# Sheet3.net
KiCad netlist of a schematic drawn in Altium Designer
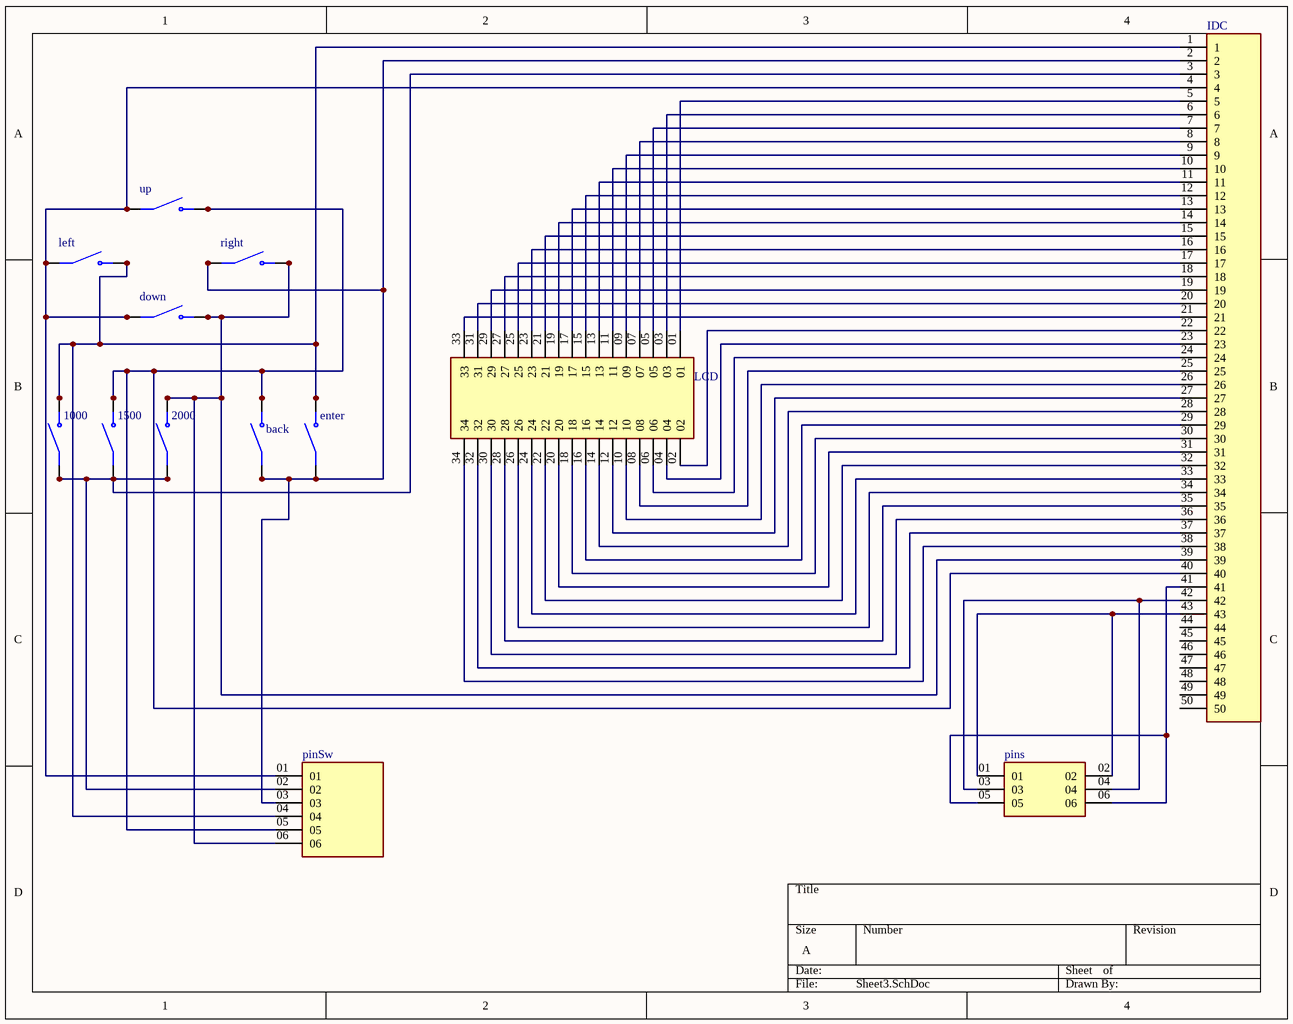
[diagram p0: Sheet3.SchDoc]

(export (version "E")
  (design (tool "Eeschema 10.0.6"))
  (components
    (comp (ref "1000")
      (value "4-1437565-9")
      (footprint "SW_4-1437565-9")
      (fields (field (name "MF") "TE Connectivity"))
      (libsource (lib "sw4") (part "4-1437565-9"))
    )
    (comp (ref "1500")
      (value "4-1437565-9")
      (footprint "SW_4-1437565-9")
      (fields (field (name "MF") "TE Connectivity"))
      (libsource (lib "sw4") (part "4-1437565-9"))
    )
    (comp (ref "2000")
      (value "4-1437565-9")
      (footprint "SW_4-1437565-9")
      (fields (field (name "MF") "TE Connectivity"))
      (libsource (lib "sw4") (part "4-1437565-9"))
    )
    (comp (ref "back")
      (value "4-1437565-9")
      (footprint "SW_4-1437565-9")
      (fields (field (name "MF") "TE Connectivity"))
      (libsource (lib "sw4") (part "4-1437565-9"))
    )
    (comp (ref "down")
      (value "4-1437565-9")
      (footprint "SW_4-1437565-9")
      (fields (field (name "MF") "TE Connectivity"))
      (libsource (lib "sw4") (part "4-1437565-9"))
    )
    (comp (ref "enter")
      (value "4-1437565-9")
      (footprint "SW_4-1437565-9")
      (fields (field (name "MF") "TE Connectivity"))
      (libsource (lib "sw4") (part "4-1437565-9"))
    )
    (comp (ref "IDC")
      (value "1-1761686-5")
      (footprint "TE_1-1761686-5")
      (libsource (lib "50pin") (part "1-1761686-5"))
    )
    (comp (ref "LCD")
      (value "TSW-117-23-G-D")
      (footprint "SAMTEC_TSW-117-23-G-D")
      (libsource (lib "pinhdr34") (part "TSW-117-23-G-D"))
    )
    (comp (ref "left")
      (value "4-1437565-9")
      (footprint "SW_4-1437565-9")
      (fields (field (name "MF") "TE Connectivity"))
      (libsource (lib "sw4") (part "4-1437565-9"))
    )
    (comp (ref "pins")
      (value "MTLW-103-07-L-D-320")
      (footprint "SAMTEC_MTLW-103-07-L-D-320")
      (libsource (lib "6pinhdr") (part "MTLW-103-07-L-D-320"))
    )
    (comp (ref "pinSw")
      (value "MTLW-106-05-T-S-137")
      (footprint "SAMTEC_MTLW-106-05-T-S-137")
      (libsource (lib "6pins") (part "MTLW-106-05-T-S-137"))
    )
    (comp (ref "right")
      (value "4-1437565-9")
      (footprint "SW_4-1437565-9")
      (fields (field (name "MF") "TE Connectivity"))
      (libsource (lib "sw4") (part "4-1437565-9"))
    )
    (comp (ref "up")
      (value "4-1437565-9")
      (footprint "SW_4-1437565-9")
      (fields (field (name "MF") "TE Connectivity"))
      (libsource (lib "sw4") (part "4-1437565-9"))
    )
  )
  (nets
    (net (code "1") (name "Net-(1000-COM-Pad1)") (class "Default")
      (node (ref "1000") (pin "1") (pinfunction "COM_1") (pintype "passive"))
      (node (ref "1000") (pin "2") (pinfunction "COM_2") (pintype "passive"))
      (node (ref "1500") (pin "1") (pinfunction "COM_1") (pintype "passive"))
      (node (ref "1500") (pin "2") (pinfunction "COM_2") (pintype "passive"))
      (node (ref "2000") (pin "1") (pinfunction "COM_1") (pintype "passive"))
      (node (ref "2000") (pin "2") (pinfunction "COM_2") (pintype "passive"))
      (node (ref "IDC") (pin "3") (pinfunction "3_3") (pintype "passive"))
      (node (ref "pinSw") (pin "02") (pinfunction "02_02") (pintype "passive"))
    )
    (net (code "2") (name "Net-(1000-NO-Pad3)") (class "Default")
      (node (ref "1000") (pin "3") (pinfunction "NO_3") (pintype "passive"))
      (node (ref "1000") (pin "4") (pinfunction "NO_4") (pintype "passive"))
      (node (ref "IDC") (pin "1") (pinfunction "1_1") (pintype "passive"))
      (node (ref "enter") (pin "3") (pinfunction "NO_3") (pintype "passive"))
      (node (ref "enter") (pin "4") (pinfunction "NO_4") (pintype "passive"))
      (node (ref "left") (pin "3") (pinfunction "NO_3") (pintype "passive"))
      (node (ref "left") (pin "4") (pinfunction "NO_4") (pintype "passive"))
      (node (ref "pinSw") (pin "04") (pinfunction "04_04") (pintype "passive"))
    )
    (net (code "3") (name "Net-(1500-NO-Pad3)") (class "Default")
      (node (ref "1500") (pin "3") (pinfunction "NO_3") (pintype "passive"))
      (node (ref "1500") (pin "4") (pinfunction "NO_4") (pintype "passive"))
      (node (ref "IDC") (pin "40") (pinfunction "40_40") (pintype "passive"))
      (node (ref "back") (pin "3") (pinfunction "NO_3") (pintype "passive"))
      (node (ref "back") (pin "4") (pinfunction "NO_4") (pintype "passive"))
      (node (ref "pinSw") (pin "05") (pinfunction "05_05") (pintype "passive"))
      (node (ref "up") (pin "3") (pinfunction "NO_3") (pintype "passive"))
      (node (ref "up") (pin "4") (pinfunction "NO_4") (pintype "passive"))
    )
    (net (code "4") (name "Net-(2000-NO-Pad3)") (class "Default")
      (node (ref "2000") (pin "3") (pinfunction "NO_3") (pintype "passive"))
      (node (ref "2000") (pin "4") (pinfunction "NO_4") (pintype "passive"))
      (node (ref "IDC") (pin "39") (pinfunction "39_39") (pintype "passive"))
      (node (ref "down") (pin "3") (pinfunction "NO_3") (pintype "passive"))
      (node (ref "down") (pin "4") (pinfunction "NO_4") (pintype "passive"))
      (node (ref "pinSw") (pin "06") (pinfunction "06_06") (pintype "passive"))
      (node (ref "right") (pin "3") (pinfunction "NO_3") (pintype "passive"))
      (node (ref "right") (pin "4") (pinfunction "NO_4") (pintype "passive"))
    )
    (net (code "5") (name "Net-(IDC-Pad2)") (class "Default")
      (node (ref "IDC") (pin "2") (pinfunction "2_2") (pintype "passive"))
      (node (ref "back") (pin "1") (pinfunction "COM_1") (pintype "passive"))
      (node (ref "back") (pin "2") (pinfunction "COM_2") (pintype "passive"))
      (node (ref "enter") (pin "1") (pinfunction "COM_1") (pintype "passive"))
      (node (ref "enter") (pin "2") (pinfunction "COM_2") (pintype "passive"))
      (node (ref "pinSw") (pin "03") (pinfunction "03_03") (pintype "passive"))
      (node (ref "right") (pin "1") (pinfunction "COM_1") (pintype "passive"))
      (node (ref "right") (pin "2") (pinfunction "COM_2") (pintype "passive"))
    )
    (net (code "6") (name "Net-(IDC-Pad4)") (class "Default")
      (node (ref "IDC") (pin "4") (pinfunction "4_4") (pintype "passive"))
      (node (ref "down") (pin "1") (pinfunction "COM_1") (pintype "passive"))
      (node (ref "down") (pin "2") (pinfunction "COM_2") (pintype "passive"))
      (node (ref "left") (pin "1") (pinfunction "COM_1") (pintype "passive"))
      (node (ref "left") (pin "2") (pinfunction "COM_2") (pintype "passive"))
      (node (ref "pinSw") (pin "01") (pinfunction "01_01") (pintype "passive"))
      (node (ref "up") (pin "1") (pinfunction "COM_1") (pintype "passive"))
      (node (ref "up") (pin "2") (pinfunction "COM_2") (pintype "passive"))
    )
    (net (code "7") (name "Net-(IDC-Pad5)") (class "Default")
      (node (ref "IDC") (pin "5") (pinfunction "5_5") (pintype "passive"))
      (node (ref "LCD") (pin "01") (pinfunction "01_01") (pintype "passive"))
    )
    (net (code "8") (name "Net-(IDC-Pad6)") (class "Default")
      (node (ref "IDC") (pin "6") (pinfunction "6_6") (pintype "passive"))
      (node (ref "LCD") (pin "03") (pinfunction "03_03") (pintype "passive"))
    )
    (net (code "9") (name "Net-(IDC-Pad7)") (class "Default")
      (node (ref "IDC") (pin "7") (pinfunction "7_7") (pintype "passive"))
      (node (ref "LCD") (pin "05") (pinfunction "05_05") (pintype "passive"))
    )
    (net (code "10") (name "Net-(IDC-Pad8)") (class "Default")
      (node (ref "IDC") (pin "8") (pinfunction "8_8") (pintype "passive"))
      (node (ref "LCD") (pin "07") (pinfunction "07_07") (pintype "passive"))
    )
    (net (code "11") (name "Net-(IDC-Pad9)") (class "Default")
      (node (ref "IDC") (pin "9") (pinfunction "9_9") (pintype "passive"))
      (node (ref "LCD") (pin "09") (pinfunction "09_09") (pintype "passive"))
    )
    (net (code "12") (name "Net-(IDC-Pad10)") (class "Default")
      (node (ref "IDC") (pin "10") (pinfunction "10_10") (pintype "passive"))
      (node (ref "LCD") (pin "11") (pinfunction "11_11") (pintype "passive"))
    )
    (net (code "13") (name "Net-(IDC-Pad11)") (class "Default")
      (node (ref "IDC") (pin "11") (pinfunction "11_11") (pintype "passive"))
      (node (ref "LCD") (pin "13") (pinfunction "13_13") (pintype "passive"))
    )
    (net (code "14") (name "Net-(IDC-Pad12)") (class "Default")
      (node (ref "IDC") (pin "12") (pinfunction "12_12") (pintype "passive"))
      (node (ref "LCD") (pin "15") (pinfunction "15_15") (pintype "passive"))
    )
    (net (code "15") (name "Net-(IDC-Pad13)") (class "Default")
      (node (ref "IDC") (pin "13") (pinfunction "13_13") (pintype "passive"))
      (node (ref "LCD") (pin "17") (pinfunction "17_17") (pintype "passive"))
    )
    (net (code "16") (name "Net-(IDC-Pad14)") (class "Default")
      (node (ref "IDC") (pin "14") (pinfunction "14_14") (pintype "passive"))
      (node (ref "LCD") (pin "19") (pinfunction "19_19") (pintype "passive"))
    )
    (net (code "17") (name "Net-(IDC-Pad15)") (class "Default")
      (node (ref "IDC") (pin "15") (pinfunction "15_15") (pintype "passive"))
      (node (ref "LCD") (pin "21") (pinfunction "21_21") (pintype "passive"))
    )
    (net (code "18") (name "Net-(IDC-Pad16)") (class "Default")
      (node (ref "IDC") (pin "16") (pinfunction "16_16") (pintype "passive"))
      (node (ref "LCD") (pin "23") (pinfunction "23_23") (pintype "passive"))
    )
    (net (code "19") (name "Net-(IDC-Pad17)") (class "Default")
      (node (ref "IDC") (pin "17") (pinfunction "17_17") (pintype "passive"))
      (node (ref "LCD") (pin "25") (pinfunction "25_25") (pintype "passive"))
    )
    (net (code "20") (name "Net-(IDC-Pad18)") (class "Default")
      (node (ref "IDC") (pin "18") (pinfunction "18_18") (pintype "passive"))
      (node (ref "LCD") (pin "27") (pinfunction "27_27") (pintype "passive"))
    )
    (net (code "21") (name "Net-(IDC-Pad19)") (class "Default")
      (node (ref "IDC") (pin "19") (pinfunction "19_19") (pintype "passive"))
      (node (ref "LCD") (pin "29") (pinfunction "29_29") (pintype "passive"))
    )
    (net (code "22") (name "Net-(IDC-Pad20)") (class "Default")
      (node (ref "IDC") (pin "20") (pinfunction "20_20") (pintype "passive"))
      (node (ref "LCD") (pin "31") (pinfunction "31_31") (pintype "passive"))
    )
    (net (code "23") (name "Net-(IDC-Pad21)") (class "Default")
      (node (ref "IDC") (pin "21") (pinfunction "21_21") (pintype "passive"))
      (node (ref "LCD") (pin "33") (pinfunction "33_33") (pintype "passive"))
    )
    (net (code "24") (name "Net-(IDC-Pad22)") (class "Default")
      (node (ref "IDC") (pin "22") (pinfunction "22_22") (pintype "passive"))
      (node (ref "LCD") (pin "02") (pinfunction "02_02") (pintype "passive"))
    )
    (net (code "25") (name "Net-(IDC-Pad23)") (class "Default")
      (node (ref "IDC") (pin "23") (pinfunction "23_23") (pintype "passive"))
      (node (ref "LCD") (pin "04") (pinfunction "04_04") (pintype "passive"))
    )
    (net (code "26") (name "Net-(IDC-Pad24)") (class "Default")
      (node (ref "IDC") (pin "24") (pinfunction "24_24") (pintype "passive"))
      (node (ref "LCD") (pin "06") (pinfunction "06_06") (pintype "passive"))
    )
    (net (code "27") (name "Net-(IDC-Pad25)") (class "Default")
      (node (ref "IDC") (pin "25") (pinfunction "25_25") (pintype "passive"))
      (node (ref "LCD") (pin "08") (pinfunction "08_08") (pintype "passive"))
    )
    (net (code "28") (name "Net-(IDC-Pad26)") (class "Default")
      (node (ref "IDC") (pin "26") (pinfunction "26_26") (pintype "passive"))
      (node (ref "LCD") (pin "10") (pinfunction "10_10") (pintype "passive"))
    )
    (net (code "29") (name "Net-(IDC-Pad27)") (class "Default")
      (node (ref "IDC") (pin "27") (pinfunction "27_27") (pintype "passive"))
      (node (ref "LCD") (pin "12") (pinfunction "12_12") (pintype "passive"))
    )
    (net (code "30") (name "Net-(IDC-Pad28)") (class "Default")
      (node (ref "IDC") (pin "28") (pinfunction "28_28") (pintype "passive"))
      (node (ref "LCD") (pin "14") (pinfunction "14_14") (pintype "passive"))
    )
    (net (code "31") (name "Net-(IDC-Pad29)") (class "Default")
      (node (ref "IDC") (pin "29") (pinfunction "29_29") (pintype "passive"))
      (node (ref "LCD") (pin "16") (pinfunction "16_16") (pintype "passive"))
    )
    (net (code "32") (name "Net-(IDC-Pad30)") (class "Default")
      (node (ref "IDC") (pin "30") (pinfunction "30_30") (pintype "passive"))
      (node (ref "LCD") (pin "18") (pinfunction "18_18") (pintype "passive"))
    )
    (net (code "33") (name "Net-(IDC-Pad31)") (class "Default")
      (node (ref "IDC") (pin "31") (pinfunction "31_31") (pintype "passive"))
      (node (ref "LCD") (pin "20") (pinfunction "20_20") (pintype "passive"))
    )
    (net (code "34") (name "Net-(IDC-Pad32)") (class "Default")
      (node (ref "IDC") (pin "32") (pinfunction "32_32") (pintype "passive"))
      (node (ref "LCD") (pin "22") (pinfunction "22_22") (pintype "passive"))
    )
    (net (code "35") (name "Net-(IDC-Pad33)") (class "Default")
      (node (ref "IDC") (pin "33") (pinfunction "33_33") (pintype "passive"))
      (node (ref "LCD") (pin "24") (pinfunction "24_24") (pintype "passive"))
    )
    (net (code "36") (name "Net-(IDC-Pad34)") (class "Default")
      (node (ref "IDC") (pin "34") (pinfunction "34_34") (pintype "passive"))
      (node (ref "LCD") (pin "26") (pinfunction "26_26") (pintype "passive"))
    )
    (net (code "37") (name "Net-(IDC-Pad35)") (class "Default")
      (node (ref "IDC") (pin "35") (pinfunction "35_35") (pintype "passive"))
      (node (ref "LCD") (pin "28") (pinfunction "28_28") (pintype "passive"))
    )
    (net (code "38") (name "Net-(IDC-Pad36)") (class "Default")
      (node (ref "IDC") (pin "36") (pinfunction "36_36") (pintype "passive"))
      (node (ref "LCD") (pin "30") (pinfunction "30_30") (pintype "passive"))
    )
    (net (code "39") (name "Net-(IDC-Pad37)") (class "Default")
      (node (ref "IDC") (pin "37") (pinfunction "37_37") (pintype "passive"))
      (node (ref "LCD") (pin "32") (pinfunction "32_32") (pintype "passive"))
    )
    (net (code "40") (name "Net-(IDC-Pad38)") (class "Default")
      (node (ref "IDC") (pin "38") (pinfunction "38_38") (pintype "passive"))
      (node (ref "LCD") (pin "34") (pinfunction "34_34") (pintype "passive"))
    )
    (net (code "41") (name "Net-(IDC-Pad41)") (class "Default")
      (node (ref "IDC") (pin "41") (pinfunction "41_41") (pintype "passive"))
      (node (ref "pins") (pin "05") (pinfunction "05_05") (pintype "passive"))
      (node (ref "pins") (pin "06") (pinfunction "06_06") (pintype "passive"))
    )
    (net (code "42") (name "Net-(IDC-Pad42)") (class "Default")
      (node (ref "IDC") (pin "42") (pinfunction "42_42") (pintype "passive"))
      (node (ref "pins") (pin "03") (pinfunction "03_03") (pintype "passive"))
      (node (ref "pins") (pin "04") (pinfunction "04_04") (pintype "passive"))
    )
    (net (code "43") (name "Net-(IDC-Pad43)") (class "Default")
      (node (ref "IDC") (pin "43") (pinfunction "43_43") (pintype "passive"))
      (node (ref "pins") (pin "01") (pinfunction "01_01") (pintype "passive"))
      (node (ref "pins") (pin "02") (pinfunction "02_02") (pintype "passive"))
    )
    (net (code "44") (name "unconnected-(IDC-Pad44)") (class "Default")
      (node (ref "IDC") (pin "44") (pinfunction "44_44") (pintype "passive"))
    )
    (net (code "45") (name "unconnected-(IDC-Pad45)") (class "Default")
      (node (ref "IDC") (pin "45") (pinfunction "45_45") (pintype "passive"))
    )
    (net (code "46") (name "unconnected-(IDC-Pad46)") (class "Default")
      (node (ref "IDC") (pin "46") (pinfunction "46_46") (pintype "passive"))
    )
    (net (code "47") (name "unconnected-(IDC-Pad47)") (class "Default")
      (node (ref "IDC") (pin "47") (pinfunction "47_47") (pintype "passive"))
    )
    (net (code "48") (name "unconnected-(IDC-Pad48)") (class "Default")
      (node (ref "IDC") (pin "48") (pinfunction "48_48") (pintype "passive"))
    )
    (net (code "49") (name "unconnected-(IDC-Pad49)") (class "Default")
      (node (ref "IDC") (pin "49") (pinfunction "49_49") (pintype "passive"))
    )
    (net (code "50") (name "unconnected-(IDC-Pad50)") (class "Default")
      (node (ref "IDC") (pin "50") (pinfunction "50_50") (pintype "passive"))
    )
  )
)
